# quadrature-QCN-19.net
KiCad netlist of a schematic drawn in EAGLE
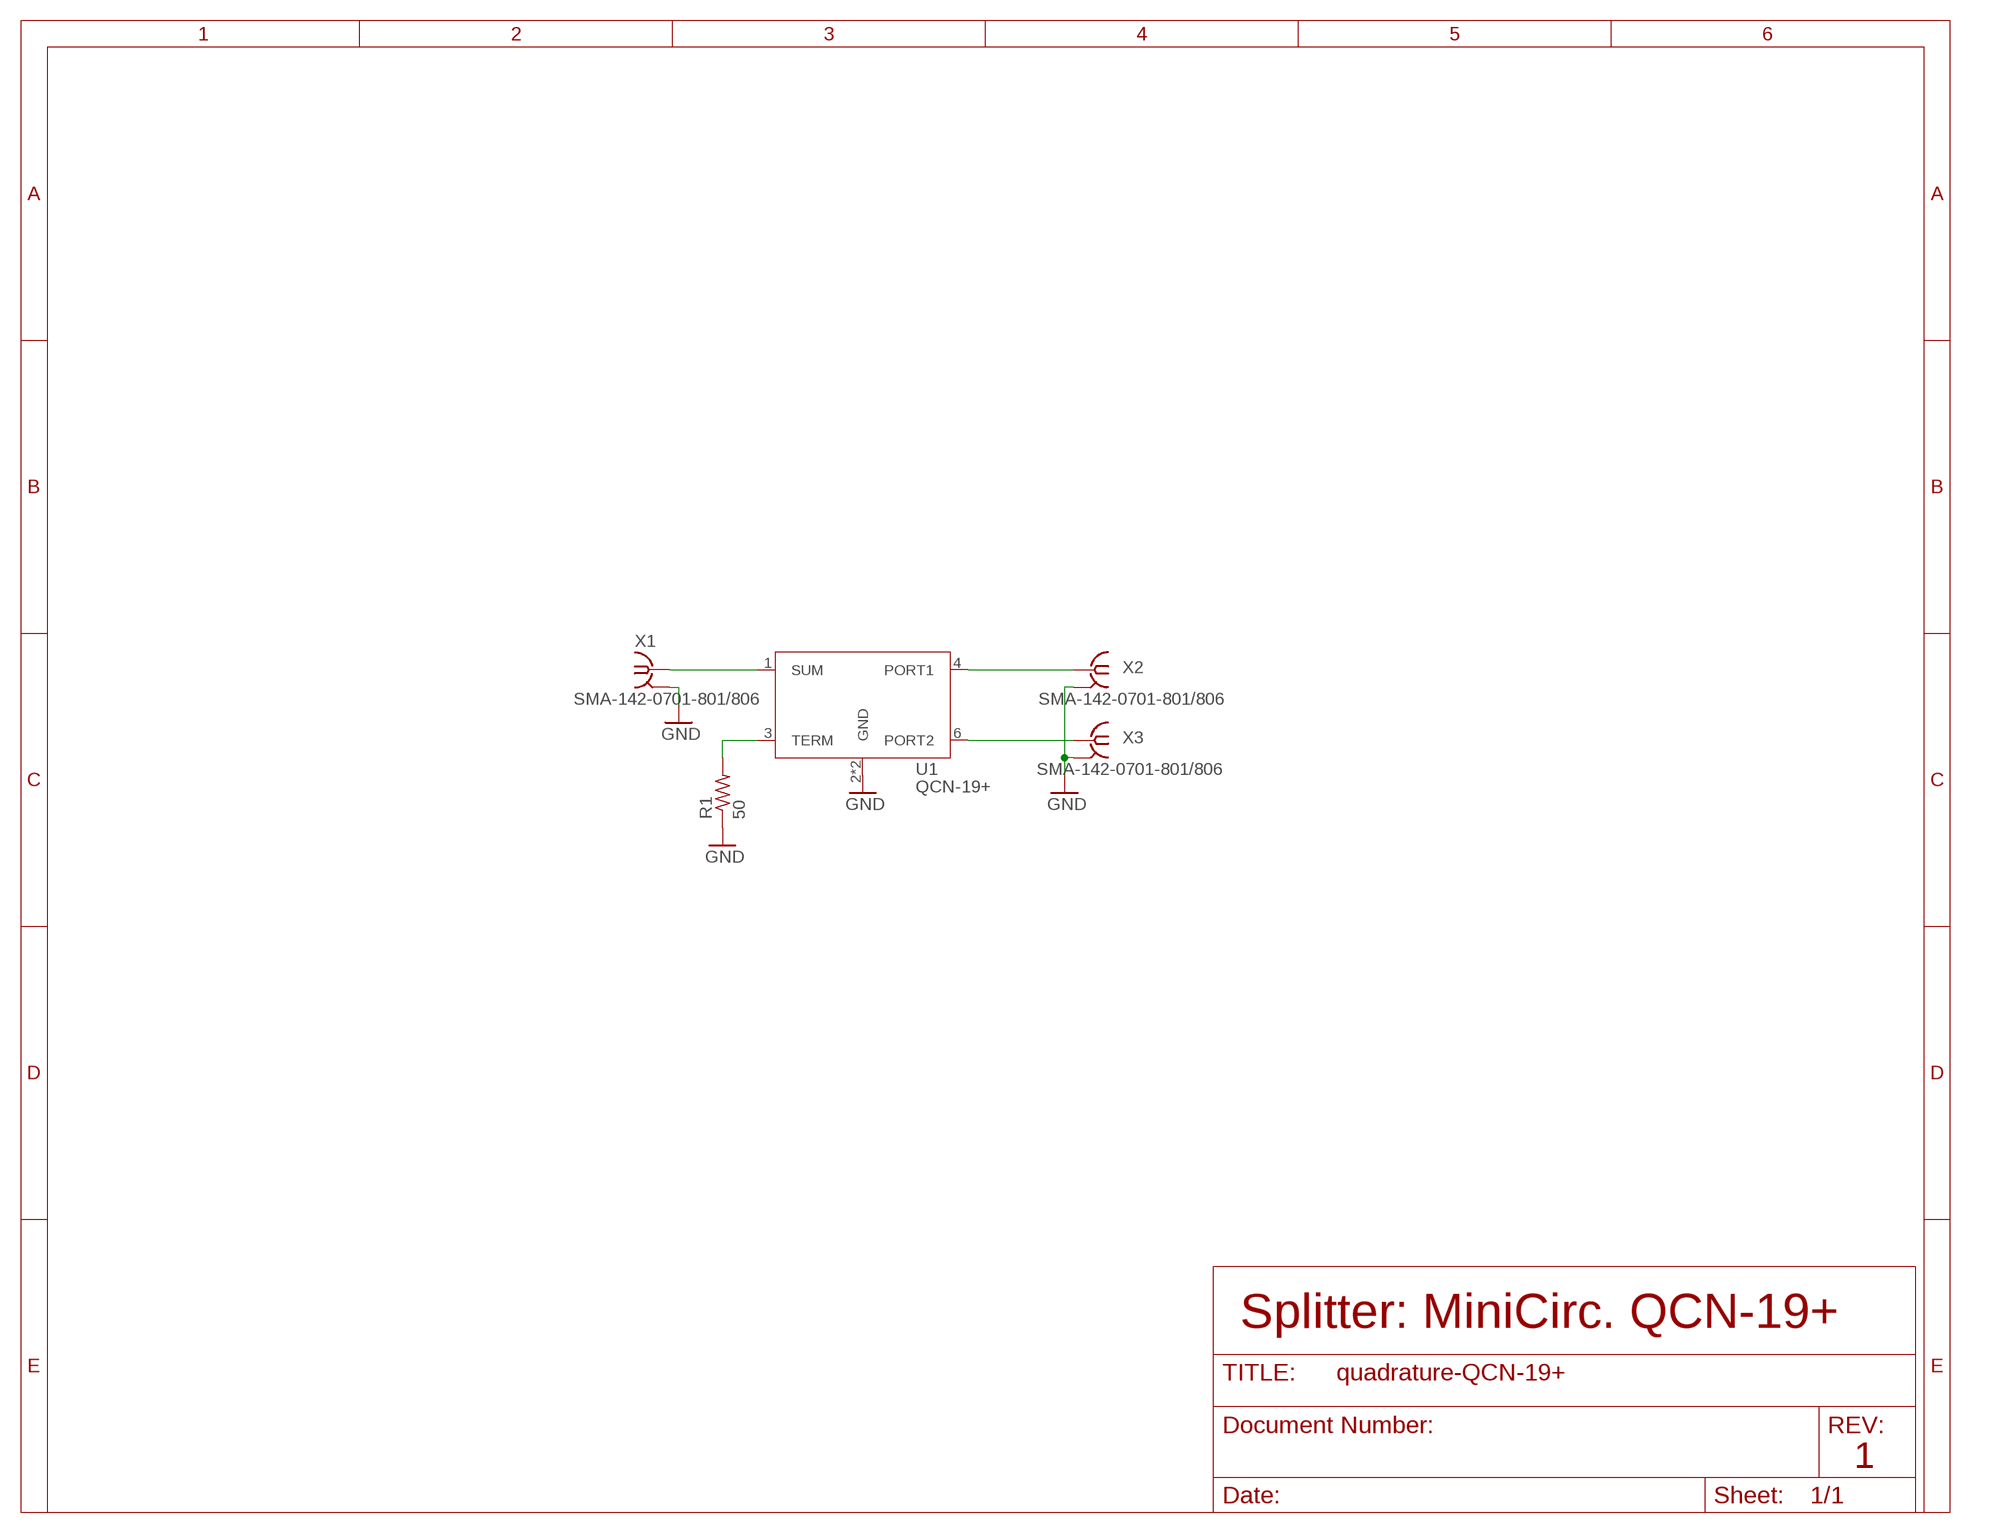
[diagram p0: schematic, sheet 1]

(export (version "E")
  (design (tool "Eeschema 10.0.6"))
  (components
    (comp (ref "R1")
      (value "50")
      (footprint "eagle-import:.0402-B-NOSILK")
      (libsource (lib "eagle-import") (part "R-US_0402-B-NOSILK"))
    )
    (comp (ref "U1")
      (value "QCN-19+")
      (footprint "eagle-import:QCN-19+")
      (libsource (lib "eagle-import") (part "QCN-19+"))
    )
    (comp (ref "X1")
      (value "SMA-142-0701-801/806")
      (footprint "eagle-import:J502-ND-142-0701-801_806")
      (fields (field (name "MF") "JOHNSON COMPONENTS") (field (name "MPN") "142-0701-801"))
      (libsource (lib "eagle-import") (part "SMA-142-0701-801/806"))
    )
    (comp (ref "X2")
      (value "SMA-142-0701-801/806")
      (footprint "eagle-import:J502-ND-142-0701-801_806")
      (fields (field (name "MF") "JOHNSON COMPONENTS") (field (name "MPN") "142-0701-801"))
      (libsource (lib "eagle-import") (part "SMA-142-0701-801/806"))
    )
    (comp (ref "X3")
      (value "SMA-142-0701-801/806")
      (footprint "eagle-import:J502-ND-142-0701-801_806")
      (fields (field (name "MF") "JOHNSON COMPONENTS") (field (name "MPN") "142-0701-801"))
      (libsource (lib "eagle-import") (part "SMA-142-0701-801/806"))
    )
  )
  (nets
    (net (code "1") (name "GND") (class "Default")
      (node (ref "R1") (pin "1") (pinfunction "1_1") (pintype "passive"))
      (node (ref "U1") (pin "2") (pinfunction "GND_2") (pintype "power_in"))
      (node (ref "U1") (pin "5") (pinfunction "GND_5") (pintype "power_in"))
      (node (ref "X1") (pin "G@1") (pinfunction "2_G@1") (pintype "passive"))
      (node (ref "X1") (pin "G@2") (pinfunction "2_G@2") (pintype "passive"))
      (node (ref "X1") (pin "G@3") (pinfunction "2_G@3") (pintype "passive"))
      (node (ref "X1") (pin "G@4") (pinfunction "2_G@4") (pintype "passive"))
      (node (ref "X2") (pin "G@1") (pinfunction "2_G@1") (pintype "passive"))
      (node (ref "X2") (pin "G@2") (pinfunction "2_G@2") (pintype "passive"))
      (node (ref "X2") (pin "G@3") (pinfunction "2_G@3") (pintype "passive"))
      (node (ref "X2") (pin "G@4") (pinfunction "2_G@4") (pintype "passive"))
      (node (ref "X3") (pin "G@1") (pinfunction "2_G@1") (pintype "passive"))
      (node (ref "X3") (pin "G@2") (pinfunction "2_G@2") (pintype "passive"))
      (node (ref "X3") (pin "G@3") (pinfunction "2_G@3") (pintype "passive"))
      (node (ref "X3") (pin "G@4") (pinfunction "2_G@4") (pintype "passive"))
    )
    (net (code "2") (name "Net-(U1-PORT1)") (class "Default")
      (node (ref "U1") (pin "4") (pinfunction "PORT1_4") (pintype "bidirectional"))
      (node (ref "X2") (pin "1") (pinfunction "1_1") (pintype "passive"))
    )
    (net (code "3") (name "Net-(U1-PORT2)") (class "Default")
      (node (ref "U1") (pin "6") (pinfunction "PORT2_6") (pintype "bidirectional"))
      (node (ref "X3") (pin "1") (pinfunction "1_1") (pintype "passive"))
    )
    (net (code "4") (name "Net-(U1-SUM)") (class "Default")
      (node (ref "U1") (pin "1") (pinfunction "SUM_1") (pintype "bidirectional"))
      (node (ref "X1") (pin "1") (pinfunction "1_1") (pintype "passive"))
    )
    (net (code "5") (name "Net-(U1-TERM)") (class "Default")
      (node (ref "R1") (pin "2") (pinfunction "2_2") (pintype "passive"))
      (node (ref "U1") (pin "3") (pinfunction "TERM_3") (pintype "bidirectional"))
    )
  )
)
